# Geiger_counter_uC_section.net
KiCad netlist of a schematic drawn in EAGLE
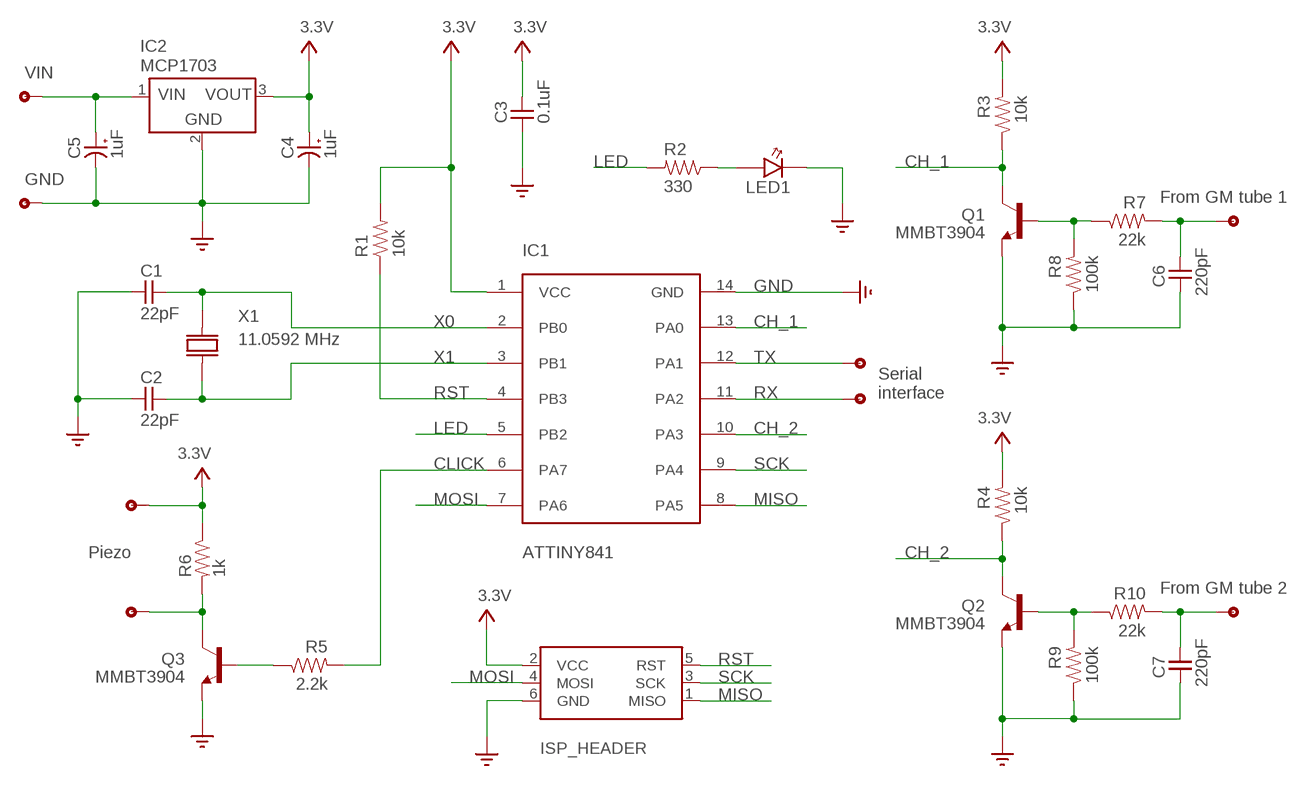
[diagram p0: schematic, sheet 1]

(export (version "E")
  (design (tool "Eeschema 10.0.6"))
  (components
    (comp (ref "C1")
      (value "22pF")
      (footprint "eagle-import:0805")
      (libsource (lib "eagle-import") (part "CAPACITOR0805"))
    )
    (comp (ref "C2")
      (value "22pF")
      (footprint "eagle-import:0805")
      (libsource (lib "eagle-import") (part "CAPACITOR0805"))
    )
    (comp (ref "C3")
      (value "0.1uF")
      (footprint "eagle-import:0805")
      (libsource (lib "eagle-import") (part "CAPACITOR0805"))
    )
    (comp (ref "C4")
      (value "1uF")
      (footprint "eagle-import:1206")
      (libsource (lib "eagle-import") (part "CAPACITOR+"))
    )
    (comp (ref "C5")
      (value "1uF")
      (footprint "eagle-import:1206")
      (libsource (lib "eagle-import") (part "CAPACITOR+"))
    )
    (comp (ref "C6")
      (value "220pF")
      (footprint "eagle-import:0805")
      (libsource (lib "eagle-import") (part "CAPACITOR0805"))
    )
    (comp (ref "C7")
      (value "220pF")
      (footprint "eagle-import:0805")
      (libsource (lib "eagle-import") (part "CAPACITOR0805"))
    )
    (comp (ref "IC1")
      (value "ATTINY841")
      (footprint "eagle-import:SO14")
      (libsource (lib "eagle-import") (part "ATTINY841SO-14"))
    )
    (comp (ref "IC2")
      (value "MCP1703")
      (footprint "eagle-import:SOT-23A")
      (libsource (lib "eagle-import") (part "MCP1703"))
    )
    (comp (ref "ISP_HEADER")
      (value "ISP header")
      (footprint "eagle-import:ISP_HEADER")
      (libsource (lib "eagle-import") (part "ISP_HEADER"))
    )
    (comp (ref "LED1")
      (value "LED0805")
      (footprint "eagle-import:0805")
      (libsource (lib "eagle-import") (part "LED0805"))
    )
    (comp (ref "Q1")
      (value "MMBT3904")
      (footprint "eagle-import:SOT-23A")
      (libsource (lib "eagle-import") (part "MMBT3904"))
    )
    (comp (ref "Q2")
      (value "MMBT3904")
      (footprint "eagle-import:SOT-23A")
      (libsource (lib "eagle-import") (part "MMBT3904"))
    )
    (comp (ref "Q3")
      (value "MMBT3904")
      (footprint "eagle-import:SOT-23A")
      (libsource (lib "eagle-import") (part "MMBT3904"))
    )
    (comp (ref "R1")
      (value "10k")
      (footprint "eagle-import:0805")
      (libsource (lib "eagle-import") (part "RESISTOR0805SMD"))
    )
    (comp (ref "R2")
      (value "330")
      (footprint "eagle-import:0805")
      (libsource (lib "eagle-import") (part "RESISTOR0805SMD"))
    )
    (comp (ref "R3")
      (value "10k")
      (footprint "eagle-import:0805")
      (libsource (lib "eagle-import") (part "RESISTOR0805SMD"))
    )
    (comp (ref "R4")
      (value "10k")
      (footprint "eagle-import:0805")
      (libsource (lib "eagle-import") (part "RESISTOR0805SMD"))
    )
    (comp (ref "R5")
      (value "2.2k")
      (footprint "eagle-import:0805")
      (libsource (lib "eagle-import") (part "RESISTOR0805SMD"))
    )
    (comp (ref "R6")
      (value "1k")
      (footprint "eagle-import:0805")
      (libsource (lib "eagle-import") (part "RESISTOR0805SMD"))
    )
    (comp (ref "R7")
      (value "22k")
      (footprint "eagle-import:0805")
      (libsource (lib "eagle-import") (part "RESISTOR0805SMD"))
    )
    (comp (ref "R8")
      (value "100k")
      (footprint "eagle-import:0805")
      (libsource (lib "eagle-import") (part "RESISTOR0805SMD"))
    )
    (comp (ref "R9")
      (value "100k")
      (footprint "eagle-import:0805")
      (libsource (lib "eagle-import") (part "RESISTOR0805SMD"))
    )
    (comp (ref "R10")
      (value "22k")
      (footprint "eagle-import:0805")
      (libsource (lib "eagle-import") (part "RESISTOR0805SMD"))
    )
    (comp (ref "TP1")
      (value "TPSMALL")
      (footprint "eagle-import:TP_SMALL")
      (libsource (lib "eagle-import") (part "TPSMALL"))
    )
    (comp (ref "TP2")
      (value "TPSMALL")
      (footprint "eagle-import:TP_SMALL")
      (libsource (lib "eagle-import") (part "TPSMALL"))
    )
    (comp (ref "TP3")
      (value "TPSMALL")
      (footprint "eagle-import:TP_SMALL")
      (libsource (lib "eagle-import") (part "TPSMALL"))
    )
    (comp (ref "TP4")
      (value "TPSMALL")
      (footprint "eagle-import:TP_SMALL")
      (libsource (lib "eagle-import") (part "TPSMALL"))
    )
    (comp (ref "TP5") (value "TP") (footprint "eagle-import:TP") (libsource (lib "eagle-import") (part "TP")))
    (comp (ref "TP6") (value "TP") (footprint "eagle-import:TP") (libsource (lib "eagle-import") (part "TP")))
    (comp (ref "TP7")
      (value "TPSMALL")
      (footprint "eagle-import:TP_SMALL")
      (libsource (lib "eagle-import") (part "TPSMALL"))
    )
    (comp (ref "TP8")
      (value "TPSMALL")
      (footprint "eagle-import:TP_SMALL")
      (libsource (lib "eagle-import") (part "TPSMALL"))
    )
    (comp (ref "X1")
      (value "11.0592 MHz")
      (footprint "eagle-import:ABM3-2SMD")
      (libsource (lib "eagle-import") (part "ABM3"))
    )
  )
  (nets
    (net (code "1") (name "/CH_1") (class "Default")
      (node (ref "IC1") (pin "13") (pinfunction "PA0_13") (pintype "bidirectional"))
      (node (ref "Q1") (pin "1") (pinfunction "C_1") (pintype "passive"))
      (node (ref "R3") (pin "1") (pinfunction "1_1") (pintype "passive"))
    )
    (net (code "2") (name "/CH_2") (class "Default")
      (node (ref "IC1") (pin "10") (pinfunction "PA3_10") (pintype "bidirectional"))
      (node (ref "Q2") (pin "1") (pinfunction "C_1") (pintype "passive"))
      (node (ref "R4") (pin "1") (pinfunction "1_1") (pintype "passive"))
    )
    (net (code "3") (name "/CLICK") (class "Default")
      (node (ref "IC1") (pin "6") (pinfunction "PA7_6") (pintype "bidirectional"))
      (node (ref "R5") (pin "2") (pinfunction "2_2") (pintype "passive"))
    )
    (net (code "4") (name "/LED") (class "Default")
      (node (ref "IC1") (pin "5") (pinfunction "PB2_5") (pintype "bidirectional"))
      (node (ref "R2") (pin "2") (pinfunction "2_2") (pintype "passive"))
    )
    (net (code "5") (name "/MISO") (class "Default")
      (node (ref "IC1") (pin "8") (pinfunction "PA5_8") (pintype "bidirectional"))
      (node (ref "ISP_HEADER") (pin "1") (pinfunction "MISO_1") (pintype "bidirectional"))
    )
    (net (code "6") (name "/MOSI") (class "Default")
      (node (ref "IC1") (pin "7") (pinfunction "PA6_7") (pintype "bidirectional"))
      (node (ref "ISP_HEADER") (pin "4") (pinfunction "MOSI_4") (pintype "bidirectional"))
    )
    (net (code "7") (name "/RST") (class "Default")
      (node (ref "IC1") (pin "4") (pinfunction "PB3_4") (pintype "bidirectional"))
      (node (ref "ISP_HEADER") (pin "5") (pinfunction "RST_5") (pintype "bidirectional"))
      (node (ref "R1") (pin "1") (pinfunction "1_1") (pintype "passive"))
    )
    (net (code "8") (name "/RX") (class "Default")
      (node (ref "IC1") (pin "11") (pinfunction "PA2_11") (pintype "bidirectional"))
      (node (ref "TP2") (pin "TP_SMALL") (pinfunction "P$1_TP_SMALL") (pintype "bidirectional"))
    )
    (net (code "9") (name "/SCK") (class "Default")
      (node (ref "IC1") (pin "9") (pinfunction "PA4_9") (pintype "bidirectional"))
      (node (ref "ISP_HEADER") (pin "3") (pinfunction "SCK_3") (pintype "bidirectional"))
    )
    (net (code "10") (name "/TX") (class "Default")
      (node (ref "IC1") (pin "12") (pinfunction "PA1_12") (pintype "bidirectional"))
      (node (ref "TP1") (pin "TP_SMALL") (pinfunction "P$1_TP_SMALL") (pintype "bidirectional"))
    )
    (net (code "11") (name "/VIN") (class "Default")
      (node (ref "C5") (pin "1") (pinfunction "1_1") (pintype "passive"))
      (node (ref "IC2") (pin "1") (pinfunction "VIN_1") (pintype "power_in"))
      (node (ref "TP7") (pin "TP_SMALL") (pinfunction "P$1_TP_SMALL") (pintype "bidirectional"))
    )
    (net (code "12") (name "/X0") (class "Default")
      (node (ref "C1") (pin "2") (pinfunction "2_2") (pintype "passive"))
      (node (ref "IC1") (pin "2") (pinfunction "PB0_2") (pintype "bidirectional"))
      (node (ref "X1") (pin "P$2") (pinfunction "2_P$2") (pintype "bidirectional"))
    )
    (net (code "13") (name "/X1") (class "Default")
      (node (ref "C2") (pin "2") (pinfunction "2_2") (pintype "passive"))
      (node (ref "IC1") (pin "3") (pinfunction "PB1_3") (pintype "bidirectional"))
      (node (ref "X1") (pin "P$1") (pinfunction "1_P$1") (pintype "bidirectional"))
    )
    (net (code "14") (name "3.3V") (class "Default")
      (node (ref "C3") (pin "2") (pinfunction "2_2") (pintype "passive"))
      (node (ref "C4") (pin "1") (pinfunction "1_1") (pintype "passive"))
      (node (ref "IC1") (pin "1") (pinfunction "VCC_1") (pintype "bidirectional"))
      (node (ref "IC2") (pin "3") (pinfunction "VOUT_3") (pintype "power_in"))
      (node (ref "ISP_HEADER") (pin "2") (pinfunction "VCC_2") (pintype "bidirectional"))
      (node (ref "R1") (pin "2") (pinfunction "2_2") (pintype "passive"))
      (node (ref "R3") (pin "2") (pinfunction "2_2") (pintype "passive"))
      (node (ref "R4") (pin "2") (pinfunction "2_2") (pintype "passive"))
      (node (ref "R6") (pin "1") (pinfunction "1_1") (pintype "passive"))
      (node (ref "TP4") (pin "TP_SMALL") (pinfunction "P$1_TP_SMALL") (pintype "bidirectional"))
    )
    (net (code "15") (name "DGND") (class "Default")
      (node (ref "C1") (pin "1") (pinfunction "1_1") (pintype "passive"))
      (node (ref "C2") (pin "1") (pinfunction "1_1") (pintype "passive"))
      (node (ref "C3") (pin "1") (pinfunction "1_1") (pintype "passive"))
      (node (ref "C4") (pin "2") (pinfunction "2_2") (pintype "passive"))
      (node (ref "C5") (pin "2") (pinfunction "2_2") (pintype "passive"))
      (node (ref "C6") (pin "2") (pinfunction "2_2") (pintype "passive"))
      (node (ref "C7") (pin "2") (pinfunction "2_2") (pintype "passive"))
      (node (ref "IC1") (pin "14") (pinfunction "GND_14") (pintype "bidirectional"))
      (node (ref "IC2") (pin "2") (pinfunction "GND_2") (pintype "power_in"))
      (node (ref "ISP_HEADER") (pin "6") (pinfunction "GND_6") (pintype "bidirectional"))
      (node (ref "LED1") (pin "2") (pinfunction "K_2") (pintype "bidirectional"))
      (node (ref "Q1") (pin "3") (pinfunction "E_3") (pintype "passive"))
      (node (ref "Q2") (pin "3") (pinfunction "E_3") (pintype "passive"))
      (node (ref "Q3") (pin "3") (pinfunction "E_3") (pintype "passive"))
      (node (ref "R8") (pin "1") (pinfunction "1_1") (pintype "passive"))
      (node (ref "R9") (pin "1") (pinfunction "1_1") (pintype "passive"))
      (node (ref "TP8") (pin "TP_SMALL") (pinfunction "P$1_TP_SMALL") (pintype "bidirectional"))
    )
    (net (code "16") (name "Net-(C6-Pad1)") (class "Default")
      (node (ref "C6") (pin "1") (pinfunction "1_1") (pintype "passive"))
      (node (ref "R7") (pin "2") (pinfunction "2_2") (pintype "passive"))
      (node (ref "TP5") (pin "P$1") (pinfunction "P$1_P$1") (pintype "bidirectional"))
    )
    (net (code "17") (name "Net-(C7-Pad1)") (class "Default")
      (node (ref "C7") (pin "1") (pinfunction "1_1") (pintype "passive"))
      (node (ref "R10") (pin "2") (pinfunction "2_2") (pintype "passive"))
      (node (ref "TP6") (pin "P$1") (pinfunction "P$1_P$1") (pintype "bidirectional"))
    )
    (net (code "18") (name "Net-(LED1-A)") (class "Default")
      (node (ref "LED1") (pin "1") (pinfunction "A_1") (pintype "bidirectional"))
      (node (ref "R2") (pin "1") (pinfunction "1_1") (pintype "passive"))
    )
    (net (code "19") (name "Net-(Q1-B)") (class "Default")
      (node (ref "Q1") (pin "2") (pinfunction "B_2") (pintype "passive"))
      (node (ref "R7") (pin "1") (pinfunction "1_1") (pintype "passive"))
      (node (ref "R8") (pin "2") (pinfunction "2_2") (pintype "passive"))
    )
    (net (code "20") (name "Net-(Q2-B)") (class "Default")
      (node (ref "Q2") (pin "2") (pinfunction "B_2") (pintype "passive"))
      (node (ref "R10") (pin "1") (pinfunction "1_1") (pintype "passive"))
      (node (ref "R9") (pin "2") (pinfunction "2_2") (pintype "passive"))
    )
    (net (code "21") (name "Net-(Q3-B)") (class "Default")
      (node (ref "Q3") (pin "2") (pinfunction "B_2") (pintype "passive"))
      (node (ref "R5") (pin "1") (pinfunction "1_1") (pintype "passive"))
    )
    (net (code "22") (name "Net-(Q3-C)") (class "Default")
      (node (ref "Q3") (pin "1") (pinfunction "C_1") (pintype "passive"))
      (node (ref "R6") (pin "2") (pinfunction "2_2") (pintype "passive"))
      (node (ref "TP3") (pin "TP_SMALL") (pinfunction "P$1_TP_SMALL") (pintype "bidirectional"))
    )
  )
)
